# xc9572_dev_board_a.net
KiCad netlist of a schematic drawn in EAGLE
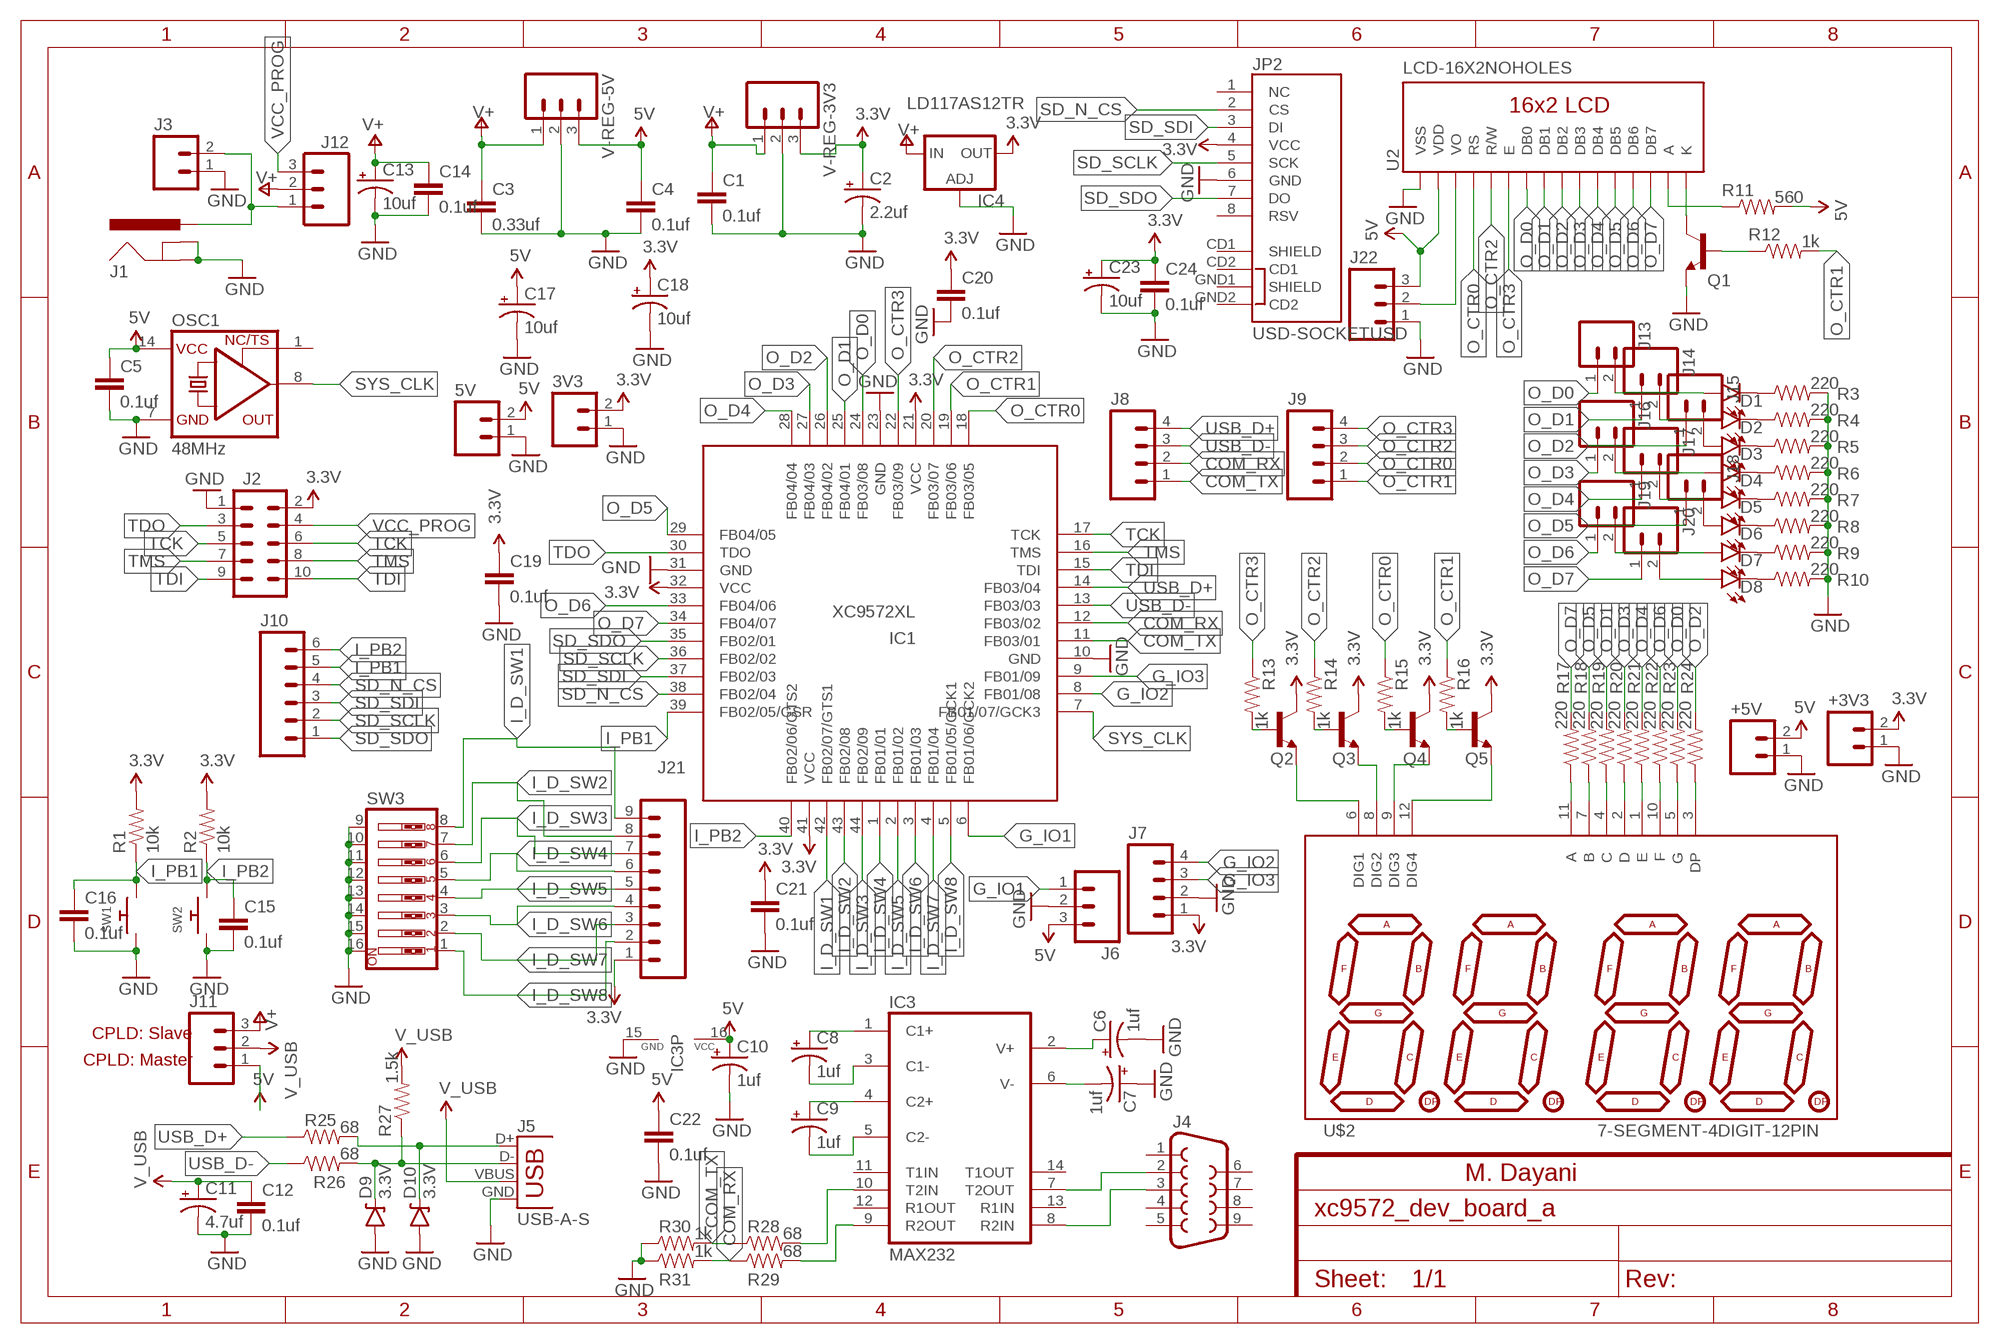
[diagram p0: schematic, sheet 1]

(export (version "E")
  (design (tool "Eeschema 10.0.6"))
  (components
    (comp (ref "+3V3")
      (value "M02JST-PTH-VERT")
      (footprint "eagle-import:JST-2-PTH-VERT")
      (libsource (lib "eagle-import") (part "M02JST-PTH-VERT"))
    )
    (comp (ref "+5V")
      (value "M02JST-PTH-VERT")
      (footprint "eagle-import:JST-2-PTH-VERT")
      (libsource (lib "eagle-import") (part "M02JST-PTH-VERT"))
    )
    (comp (ref "3V3")
      (value "M02PTH")
      (footprint "eagle-import:1X02")
      (libsource (lib "eagle-import") (part "M02PTH"))
    )
    (comp (ref "5V")
      (value "M02PTH")
      (footprint "eagle-import:1X02")
      (libsource (lib "eagle-import") (part "M02PTH"))
    )
    (comp (ref "C1")
      (value "0.1uf")
      (footprint "eagle-import:1206")
      (libsource (lib "eagle-import") (part "CAP1206"))
    )
    (comp (ref "C2")
      (value "2.2uf")
      (footprint "eagle-import:EIA3216")
      (libsource (lib "eagle-import") (part "CAP_POL1206"))
    )
    (comp (ref "C3")
      (value "0.33uf")
      (footprint "eagle-import:1206")
      (libsource (lib "eagle-import") (part "CAP1206"))
    )
    (comp (ref "C4")
      (value "0.1uf")
      (footprint "eagle-import:1206")
      (libsource (lib "eagle-import") (part "CAP1206"))
    )
    (comp (ref "C5")
      (value "0.1uf")
      (footprint "eagle-import:1206")
      (libsource (lib "eagle-import") (part "CAP1206"))
    )
    (comp (ref "C6")
      (value "1uf")
      (footprint "eagle-import:EIA3216")
      (libsource (lib "eagle-import") (part "CAP_POL1206"))
    )
    (comp (ref "C7")
      (value "1uf")
      (footprint "eagle-import:EIA3216")
      (libsource (lib "eagle-import") (part "CAP_POL1206"))
    )
    (comp (ref "C8")
      (value "1uf")
      (footprint "eagle-import:EIA3216")
      (libsource (lib "eagle-import") (part "CAP_POL1206"))
    )
    (comp (ref "C9")
      (value "1uf")
      (footprint "eagle-import:EIA3216")
      (libsource (lib "eagle-import") (part "CAP_POL1206"))
    )
    (comp (ref "C10")
      (value "1uf")
      (footprint "eagle-import:EIA3216")
      (libsource (lib "eagle-import") (part "CAP_POL1206"))
    )
    (comp (ref "C11")
      (value "4.7uf")
      (footprint "eagle-import:EIA3216")
      (libsource (lib "eagle-import") (part "CAP_POL1206"))
    )
    (comp (ref "C12")
      (value "0.1uf")
      (footprint "eagle-import:1206")
      (libsource (lib "eagle-import") (part "CAP1206"))
    )
    (comp (ref "C13")
      (value "10uf")
      (footprint "eagle-import:EIA3216")
      (libsource (lib "eagle-import") (part "CAP_POL1206"))
    )
    (comp (ref "C14")
      (value "0.1uf")
      (footprint "eagle-import:1206")
      (libsource (lib "eagle-import") (part "CAP1206"))
    )
    (comp (ref "C15")
      (value "0.1uf")
      (footprint "eagle-import:1206")
      (libsource (lib "eagle-import") (part "CAP1206"))
    )
    (comp (ref "C16")
      (value "0.1uf")
      (footprint "eagle-import:1206")
      (libsource (lib "eagle-import") (part "CAP1206"))
    )
    (comp (ref "C17")
      (value "10uf")
      (footprint "eagle-import:EIA3216")
      (libsource (lib "eagle-import") (part "CAP_POL1206"))
    )
    (comp (ref "C18")
      (value "10uf")
      (footprint "eagle-import:EIA3216")
      (libsource (lib "eagle-import") (part "CAP_POL1206"))
    )
    (comp (ref "C19")
      (value "0.1uf")
      (footprint "eagle-import:1206")
      (libsource (lib "eagle-import") (part "CAP1206"))
    )
    (comp (ref "C20")
      (value "0.1uf")
      (footprint "eagle-import:1206")
      (libsource (lib "eagle-import") (part "CAP1206"))
    )
    (comp (ref "C21")
      (value "0.1uf")
      (footprint "eagle-import:1206")
      (libsource (lib "eagle-import") (part "CAP1206"))
    )
    (comp (ref "C22")
      (value "0.1uf")
      (footprint "eagle-import:1206")
      (libsource (lib "eagle-import") (part "CAP1206"))
    )
    (comp (ref "C23")
      (value "10uf")
      (footprint "eagle-import:EIA3216")
      (libsource (lib "eagle-import") (part "CAP_POL1206"))
    )
    (comp (ref "C24")
      (value "0.1uf")
      (footprint "eagle-import:1206")
      (libsource (lib "eagle-import") (part "CAP1206"))
    )
    (comp (ref "D1")
      (value "LED1206")
      (footprint "eagle-import:LED-1206")
      (libsource (lib "eagle-import") (part "LED1206"))
    )
    (comp (ref "D2")
      (value "LED1206")
      (footprint "eagle-import:LED-1206")
      (libsource (lib "eagle-import") (part "LED1206"))
    )
    (comp (ref "D3")
      (value "LED1206")
      (footprint "eagle-import:LED-1206")
      (libsource (lib "eagle-import") (part "LED1206"))
    )
    (comp (ref "D4")
      (value "LED1206")
      (footprint "eagle-import:LED-1206")
      (libsource (lib "eagle-import") (part "LED1206"))
    )
    (comp (ref "D5")
      (value "LED1206")
      (footprint "eagle-import:LED-1206")
      (libsource (lib "eagle-import") (part "LED1206"))
    )
    (comp (ref "D6")
      (value "LED1206")
      (footprint "eagle-import:LED-1206")
      (libsource (lib "eagle-import") (part "LED1206"))
    )
    (comp (ref "D7")
      (value "LED1206")
      (footprint "eagle-import:LED-1206")
      (libsource (lib "eagle-import") (part "LED1206"))
    )
    (comp (ref "D8")
      (value "LED1206")
      (footprint "eagle-import:LED-1206")
      (libsource (lib "eagle-import") (part "LED1206"))
    )
    (comp (ref "D9")
      (value "3.3V")
      (footprint "eagle-import:SOD-323")
      (libsource (lib "eagle-import") (part "DIODE-ZENER3.3V"))
    )
    (comp (ref "D10")
      (value "3.3V")
      (footprint "eagle-import:SOD-323")
      (libsource (lib "eagle-import") (part "DIODE-ZENER3.3V"))
    )
    (comp (ref "IC1")
      (value "XC9572XL")
      (footprint "eagle-import:PLCC-S44")
      (libsource (lib "eagle-import") (part "XC9572XL"))
    )
    (comp (ref "IC3")
      (value "MAX232")
      (footprint "eagle-import:DIL16")
      (fields (field (name "MF") "MAXIM") (field (name "MPN") "MAX232ACPE+"))
      (libsource (lib "eagle-import") (part "MAX232"))
    )
    (comp (ref "IC4")
      (value "LD117AS12TR")
      (footprint "eagle-import:SOT223")
      (libsource (lib "eagle-import") (part "LD117A?S12TR"))
    )
    (comp (ref "J1")
      (value "POWER_JACKPTH_BREAD")
      (footprint "eagle-import:POWER_JACK_PTH_BREAD")
      (libsource (lib "eagle-import") (part "POWER_JACKPTH_BREAD"))
    )
    (comp (ref "J2")
      (value "M05X2SHD")
      (footprint "eagle-import:2X5-SHROUDED")
      (libsource (lib "eagle-import") (part "M05X2SHD"))
    )
    (comp (ref "J3")
      (value "M02JST-PTH-VERT")
      (footprint "eagle-import:JST-2-PTH-VERT")
      (libsource (lib "eagle-import") (part "M02JST-PTH-VERT"))
    )
    (comp (ref "J4")
      (value "DB9FEMALE")
      (footprint "eagle-import:DB9")
      (libsource (lib "eagle-import") (part "DB9FEMALE"))
    )
    (comp (ref "J5")
      (value "USB-A-S")
      (footprint "eagle-import:USB-A-S")
      (libsource (lib "eagle-import") (part "USB-A-S"))
    )
    (comp (ref "J6")
      (value "M03PTH")
      (footprint "eagle-import:1X03")
      (libsource (lib "eagle-import") (part "M03PTH"))
    )
    (comp (ref "J7")
      (value "M04PTH")
      (footprint "eagle-import:1X04")
      (libsource (lib "eagle-import") (part "M04PTH"))
    )
    (comp (ref "J8")
      (value "M04PTH")
      (footprint "eagle-import:1X04")
      (libsource (lib "eagle-import") (part "M04PTH"))
    )
    (comp (ref "J9")
      (value "M04PTH")
      (footprint "eagle-import:1X04")
      (libsource (lib "eagle-import") (part "M04PTH"))
    )
    (comp (ref "J10")
      (value "M06SILK_FEMALE_PTH")
      (footprint "eagle-import:1X06")
      (libsource (lib "eagle-import") (part "M06SILK_FEMALE_PTH"))
    )
    (comp (ref "J11")
      (value "M03PTH")
      (footprint "eagle-import:1X03")
      (libsource (lib "eagle-import") (part "M03PTH"))
    )
    (comp (ref "J12")
      (value "M03PTH")
      (footprint "eagle-import:1X03")
      (libsource (lib "eagle-import") (part "M03PTH"))
    )
    (comp (ref "J13")
      (value "M02PTH")
      (footprint "eagle-import:1X02")
      (libsource (lib "eagle-import") (part "M02PTH"))
    )
    (comp (ref "J14")
      (value "M02PTH")
      (footprint "eagle-import:1X02")
      (libsource (lib "eagle-import") (part "M02PTH"))
    )
    (comp (ref "J15")
      (value "M02PTH")
      (footprint "eagle-import:1X02")
      (libsource (lib "eagle-import") (part "M02PTH"))
    )
    (comp (ref "J16")
      (value "M02PTH")
      (footprint "eagle-import:1X02")
      (libsource (lib "eagle-import") (part "M02PTH"))
    )
    (comp (ref "J17")
      (value "M02PTH")
      (footprint "eagle-import:1X02")
      (libsource (lib "eagle-import") (part "M02PTH"))
    )
    (comp (ref "J18")
      (value "M02PTH")
      (footprint "eagle-import:1X02")
      (libsource (lib "eagle-import") (part "M02PTH"))
    )
    (comp (ref "J19")
      (value "M02PTH")
      (footprint "eagle-import:1X02")
      (libsource (lib "eagle-import") (part "M02PTH"))
    )
    (comp (ref "J20")
      (value "M02PTH")
      (footprint "eagle-import:1X02")
      (libsource (lib "eagle-import") (part "M02PTH"))
    )
    (comp (ref "J21")
      (value "M09")
      (footprint "eagle-import:1X09")
      (libsource (lib "eagle-import") (part "M09"))
    )
    (comp (ref "J22")
      (value "M03POLAR")
      (footprint "eagle-import:MOLEX-1X3")
      (libsource (lib "eagle-import") (part "M03POLAR"))
    )
    (comp (ref "JP2")
      (value "USD-SOCKETUSD")
      (footprint "eagle-import:USD-SOCKET-PP")
      (libsource (lib "eagle-import") (part "USD-SOCKETUSD"))
    )
    (comp (ref "OSC1")
      (value "48MHz")
      (footprint "eagle-import:DIL14S")
      (libsource (lib "eagle-import") (part "XO-14"))
    )
    (comp (ref "Q1")
      (value "TRANSISTOR_NPNSOT23-3")
      (footprint "eagle-import:SOT23-3")
      (libsource (lib "eagle-import") (part "TRANSISTOR_NPNSOT23-3"))
    )
    (comp (ref "Q2")
      (value "TRANSISTOR_NPNSOT23-3")
      (footprint "eagle-import:SOT23-3")
      (libsource (lib "eagle-import") (part "TRANSISTOR_NPNSOT23-3"))
    )
    (comp (ref "Q3")
      (value "TRANSISTOR_NPNSOT23-3")
      (footprint "eagle-import:SOT23-3")
      (libsource (lib "eagle-import") (part "TRANSISTOR_NPNSOT23-3"))
    )
    (comp (ref "Q4")
      (value "TRANSISTOR_NPNSOT23-3")
      (footprint "eagle-import:SOT23-3")
      (libsource (lib "eagle-import") (part "TRANSISTOR_NPNSOT23-3"))
    )
    (comp (ref "Q5")
      (value "TRANSISTOR_NPNSOT23-3")
      (footprint "eagle-import:SOT23-3")
      (libsource (lib "eagle-import") (part "TRANSISTOR_NPNSOT23-3"))
    )
    (comp (ref "R1")
      (value "10k")
      (footprint "eagle-import:1206")
      (libsource (lib "eagle-import") (part "RESISTOR1206"))
    )
    (comp (ref "R2")
      (value "10k")
      (footprint "eagle-import:1206")
      (libsource (lib "eagle-import") (part "RESISTOR1206"))
    )
    (comp (ref "R3")
      (value "220")
      (footprint "eagle-import:1206")
      (libsource (lib "eagle-import") (part "RESISTOR1206"))
    )
    (comp (ref "R4")
      (value "220")
      (footprint "eagle-import:1206")
      (libsource (lib "eagle-import") (part "RESISTOR1206"))
    )
    (comp (ref "R5")
      (value "220")
      (footprint "eagle-import:1206")
      (libsource (lib "eagle-import") (part "RESISTOR1206"))
    )
    (comp (ref "R6")
      (value "220")
      (footprint "eagle-import:1206")
      (libsource (lib "eagle-import") (part "RESISTOR1206"))
    )
    (comp (ref "R7")
      (value "220")
      (footprint "eagle-import:1206")
      (libsource (lib "eagle-import") (part "RESISTOR1206"))
    )
    (comp (ref "R8")
      (value "220")
      (footprint "eagle-import:1206")
      (libsource (lib "eagle-import") (part "RESISTOR1206"))
    )
    (comp (ref "R9")
      (value "220")
      (footprint "eagle-import:1206")
      (libsource (lib "eagle-import") (part "RESISTOR1206"))
    )
    (comp (ref "R10")
      (value "220")
      (footprint "eagle-import:1206")
      (libsource (lib "eagle-import") (part "RESISTOR1206"))
    )
    (comp (ref "R11")
      (value "560")
      (footprint "eagle-import:1206")
      (libsource (lib "eagle-import") (part "RESISTOR1206"))
    )
    (comp (ref "R12")
      (value "1k")
      (footprint "eagle-import:1206")
      (libsource (lib "eagle-import") (part "RESISTOR1206"))
    )
    (comp (ref "R13")
      (value "1k")
      (footprint "eagle-import:1206")
      (libsource (lib "eagle-import") (part "RESISTOR1206"))
    )
    (comp (ref "R14")
      (value "1k")
      (footprint "eagle-import:1206")
      (libsource (lib "eagle-import") (part "RESISTOR1206"))
    )
    (comp (ref "R15")
      (value "1k")
      (footprint "eagle-import:1206")
      (libsource (lib "eagle-import") (part "RESISTOR1206"))
    )
    (comp (ref "R16")
      (value "1k")
      (footprint "eagle-import:1206")
      (libsource (lib "eagle-import") (part "RESISTOR1206"))
    )
    (comp (ref "R17")
      (value "220")
      (footprint "eagle-import:1206")
      (libsource (lib "eagle-import") (part "RESISTOR1206"))
    )
    (comp (ref "R18")
      (value "220")
      (footprint "eagle-import:1206")
      (libsource (lib "eagle-import") (part "RESISTOR1206"))
    )
    (comp (ref "R19")
      (value "220")
      (footprint "eagle-import:1206")
      (libsource (lib "eagle-import") (part "RESISTOR1206"))
    )
    (comp (ref "R20")
      (value "220")
      (footprint "eagle-import:1206")
      (libsource (lib "eagle-import") (part "RESISTOR1206"))
    )
    (comp (ref "R21")
      (value "220")
      (footprint "eagle-import:1206")
      (libsource (lib "eagle-import") (part "RESISTOR1206"))
    )
    (comp (ref "R22")
      (value "220")
      (footprint "eagle-import:1206")
      (libsource (lib "eagle-import") (part "RESISTOR1206"))
    )
    (comp (ref "R23")
      (value "220")
      (footprint "eagle-import:1206")
      (libsource (lib "eagle-import") (part "RESISTOR1206"))
    )
    (comp (ref "R24")
      (value "220")
      (footprint "eagle-import:1206")
      (libsource (lib "eagle-import") (part "RESISTOR1206"))
    )
    (comp (ref "R25")
      (value "68")
      (footprint "eagle-import:1206")
      (libsource (lib "eagle-import") (part "RESISTOR1206"))
    )
    (comp (ref "R26")
      (value "68")
      (footprint "eagle-import:1206")
      (libsource (lib "eagle-import") (part "RESISTOR1206"))
    )
    (comp (ref "R27")
      (value "1.5k")
      (footprint "eagle-import:1206")
      (libsource (lib "eagle-import") (part "RESISTOR1206"))
    )
    (comp (ref "R28")
      (value "68")
      (footprint "eagle-import:1206")
      (libsource (lib "eagle-import") (part "RESISTOR1206"))
    )
    (comp (ref "R29")
      (value "68")
      (footprint "eagle-import:1206")
      (libsource (lib "eagle-import") (part "RESISTOR1206"))
    )
    (comp (ref "R30")
      (value "1k")
      (footprint "eagle-import:1206")
      (libsource (lib "eagle-import") (part "RESISTOR1206"))
    )
    (comp (ref "R31")
      (value "1k")
      (footprint "eagle-import:1206")
      (libsource (lib "eagle-import") (part "RESISTOR1206"))
    )
    (comp (ref "SW1")
      (value "SWITCH_PUSHBUTTONEVQ-PE")
      (footprint "eagle-import:TACT_PANA-EVQ")
      (libsource (lib "eagle-import") (part "SWITCH_PUSHBUTTONEVQ-PE"))
    )
    (comp (ref "SW2")
      (value "SWITCH_PUSHBUTTONEVQ-PE")
      (footprint "eagle-import:TACT_PANA-EVQ")
      (libsource (lib "eagle-import") (part "SWITCH_PUSHBUTTONEVQ-PE"))
    )
    (comp (ref "SW3")
      (value "SW_DIP-8")
      (footprint "eagle-import:DIPSWITCH-08")
      (libsource (lib "eagle-import") (part "SW_DIP-8"))
    )
    (comp (ref "U$2")
      (value "7-SEGMENT-4DIGIT-12PIN")
      (footprint "eagle-import:7-SEGMENT-4DIGIT-12PIN-LONGPADS")
      (libsource (lib "eagle-import") (part "7-SEGMENT-4DIGIT-12PIN"))
    )
    (comp (ref "U2")
      (value "LCD-16X2NOHOLES")
      (footprint "eagle-import:LCD-16X2_NOHOLES")
      (libsource (lib "eagle-import") (part "LCD-16X2NOHOLES"))
    )
    (comp (ref "V-REG-3V3")
      (value "M03PTH")
      (footprint "eagle-import:1X03")
      (libsource (lib "eagle-import") (part "M03PTH"))
    )
    (comp (ref "V-REG-5V")
      (value "M03PTH")
      (footprint "eagle-import:1X03")
      (libsource (lib "eagle-import") (part "M03PTH"))
    )
  )
  (nets
    (net (code "1") (name "3.3V") (class "Default")
      (node (ref "+3V3") (pin "2") (pinfunction "2_2") (pintype "passive"))
      (node (ref "3V3") (pin "2") (pinfunction "2_2") (pintype "passive"))
      (node (ref "C18") (pin "A") (pinfunction "+_A") (pintype "passive"))
      (node (ref "C19") (pin "1") (pinfunction "1_1") (pintype "passive"))
      (node (ref "C2") (pin "A") (pinfunction "+_A") (pintype "passive"))
      (node (ref "C20") (pin "1") (pinfunction "1_1") (pintype "passive"))
      (node (ref "C21") (pin "1") (pinfunction "1_1") (pintype "passive"))
      (node (ref "C23") (pin "A") (pinfunction "+_A") (pintype "passive"))
      (node (ref "C24") (pin "1") (pinfunction "1_1") (pintype "passive"))
      (node (ref "IC1") (pin "21") (pinfunction "VCC_21") (pintype "power_in"))
      (node (ref "IC1") (pin "32") (pinfunction "VCC_32") (pintype "power_in"))
      (node (ref "IC1") (pin "41") (pinfunction "VCC_41") (pintype "power_in"))
      (node (ref "IC4") (pin "4") (pinfunction "OUT_4") (pintype "passive"))
      (node (ref "J2") (pin "2") (pinfunction "2_2") (pintype "passive"))
      (node (ref "J21") (pin "1") (pinfunction "1_1") (pintype "passive"))
      (node (ref "J7") (pin "1") (pinfunction "1_1") (pintype "passive"))
      (node (ref "JP2") (pin "4") (pinfunction "VCC_4") (pintype "bidirectional"))
      (node (ref "Q2") (pin "3") (pinfunction "C_3") (pintype "passive"))
      (node (ref "Q3") (pin "3") (pinfunction "C_3") (pintype "passive"))
      (node (ref "Q4") (pin "3") (pinfunction "C_3") (pintype "passive"))
      (node (ref "Q5") (pin "3") (pinfunction "C_3") (pintype "passive"))
      (node (ref "R1") (pin "2") (pinfunction "2_2") (pintype "passive"))
      (node (ref "R2") (pin "2") (pinfunction "2_2") (pintype "passive"))
      (node (ref "V-REG-3V3") (pin "3") (pinfunction "3_3") (pintype "passive"))
    )
    (net (code "2") (name "5V") (class "Default")
      (node (ref "+5V") (pin "2") (pinfunction "2_2") (pintype "passive"))
      (node (ref "5V") (pin "2") (pinfunction "2_2") (pintype "passive"))
      (node (ref "C10") (pin "A") (pinfunction "+_A") (pintype "passive"))
      (node (ref "C17") (pin "A") (pinfunction "+_A") (pintype "passive"))
      (node (ref "C22") (pin "1") (pinfunction "1_1") (pintype "passive"))
      (node (ref "C4") (pin "1") (pinfunction "1_1") (pintype "passive"))
      (node (ref "C5") (pin "1") (pinfunction "1_1") (pintype "passive"))
      (node (ref "IC3") (pin "16") (pinfunction "VCC_16") (pintype "power_in"))
      (node (ref "J11") (pin "1") (pinfunction "1_1") (pintype "passive"))
      (node (ref "J22") (pin "3") (pinfunction "3_3") (pintype "passive"))
      (node (ref "J6") (pin "3") (pinfunction "3_3") (pintype "passive"))
      (node (ref "OSC1") (pin "14") (pinfunction "VCC_14") (pintype "power_in"))
      (node (ref "R11") (pin "2") (pinfunction "2_2") (pintype "passive"))
      (node (ref "U2") (pin "2") (pinfunction "VDD_2") (pintype "power_in"))
      (node (ref "V-REG-5V") (pin "3") (pinfunction "3_3") (pintype "passive"))
    )
    (net (code "3") (name "COM_RX") (class "Default")
      (node (ref "IC1") (pin "12") (pinfunction "FB03/02_12") (pintype "bidirectional"))
      (node (ref "J8") (pin "2") (pinfunction "2_2") (pintype "passive"))
      (node (ref "R29") (pin "1") (pinfunction "1_1") (pintype "passive"))
      (node (ref "R31") (pin "2") (pinfunction "2_2") (pintype "passive"))
    )
    (net (code "4") (name "COM_TX") (class "Default")
      (node (ref "IC1") (pin "11") (pinfunction "FB03/01_11") (pintype "bidirectional"))
      (node (ref "J8") (pin "1") (pinfunction "1_1") (pintype "passive"))
      (node (ref "R28") (pin "1") (pinfunction "1_1") (pintype "passive"))
      (node (ref "R30") (pin "2") (pinfunction "2_2") (pintype "passive"))
    )
    (net (code "5") (name "GND") (class "Default")
      (node (ref "+3V3") (pin "1") (pinfunction "1_1") (pintype "passive"))
      (node (ref "+5V") (pin "1") (pinfunction "1_1") (pintype "passive"))
      (node (ref "3V3") (pin "1") (pinfunction "1_1") (pintype "passive"))
      (node (ref "5V") (pin "1") (pinfunction "1_1") (pintype "passive"))
      (node (ref "C1") (pin "2") (pinfunction "2_2") (pintype "passive"))
      (node (ref "C10") (pin "C") (pinfunction "-_C") (pintype "passive"))
      (node (ref "C11") (pin "C") (pinfunction "-_C") (pintype "passive"))
      (node (ref "C12") (pin "2") (pinfunction "2_2") (pintype "passive"))
      (node (ref "C13") (pin "C") (pinfunction "-_C") (pintype "passive"))
      (node (ref "C14") (pin "2") (pinfunction "2_2") (pintype "passive"))
      (node (ref "C15") (pin "2") (pinfunction "2_2") (pintype "passive"))
      (node (ref "C16") (pin "2") (pinfunction "2_2") (pintype "passive"))
      (node (ref "C17") (pin "C") (pinfunction "-_C") (pintype "passive"))
      (node (ref "C18") (pin "C") (pinfunction "-_C") (pintype "passive"))
      (node (ref "C19") (pin "2") (pinfunction "2_2") (pintype "passive"))
      (node (ref "C2") (pin "C") (pinfunction "-_C") (pintype "passive"))
      (node (ref "C20") (pin "2") (pinfunction "2_2") (pintype "passive"))
      (node (ref "C21") (pin "2") (pinfunction "2_2") (pintype "passive"))
      (node (ref "C22") (pin "2") (pinfunction "2_2") (pintype "passive"))
      (node (ref "C23") (pin "C") (pinfunction "-_C") (pintype "passive"))
      (node (ref "C24") (pin "2") (pinfunction "2_2") (pintype "passive"))
      (node (ref "C3") (pin "2") (pinfunction "2_2") (pintype "passive"))
      (node (ref "C4") (pin "2") (pinfunction "2_2") (pintype "passive"))
      (node (ref "C5") (pin "2") (pinfunction "2_2") (pintype "passive"))
      (node (ref "C6") (pin "C") (pinfunction "-_C") (pintype "passive"))
      (node (ref "C7") (pin "A") (pinfunction "+_A") (pintype "passive"))
      (node (ref "D10") (pin "A") (pinfunction "A_A") (pintype "passive"))
      (node (ref "D9") (pin "A") (pinfunction "A_A") (pintype "passive"))
      (node (ref "IC1") (pin "10") (pinfunction "GND_10") (pintype "power_in"))
      (node (ref "IC1") (pin "23") (pinfunction "GND_23") (pintype "power_in"))
      (node (ref "IC1") (pin "31") (pinfunction "GND_31") (pintype "power_in"))
      (node (ref "IC3") (pin "15") (pinfunction "GND_15") (pintype "power_in"))
      (node (ref "IC4") (pin "1") (pinfunction "ADJ_1") (pintype "input"))
      (node (ref "J1") (pin "GND") (pinfunction "GND_GND") (pintype "bidirectional"))
      (node (ref "J1") (pin "GNDBREAK") (pinfunction "GNDBREAK_GNDBREAK") (pintype "bidirectional"))
      (node (ref "J2") (pin "1") (pinfunction "1_1") (pintype "passive"))
      (node (ref "J22") (pin "1") (pinfunction "1_1") (pintype "passive"))
      (node (ref "J3") (pin "1") (pinfunction "1_1") (pintype "passive"))
      (node (ref "J5") (pin "GND") (pinfunction "GND_GND") (pintype "bidirectional"))
      (node (ref "J6") (pin "2") (pinfunction "2_2") (pintype "passive"))
      (node (ref "J7") (pin "2") (pinfunction "2_2") (pintype "passive"))
      (node (ref "JP2") (pin "6") (pinfunction "GND_6") (pintype "bidirectional"))
      (node (ref "OSC1") (pin "7") (pinfunction "GND_7") (pintype "power_in"))
      (node (ref "Q1") (pin "2") (pinfunction "E_2") (pintype "passive"))
      (node (ref "R10") (pin "2") (pinfunction "2_2") (pintype "passive"))
      (node (ref "R3") (pin "2") (pinfunction "2_2") (pintype "passive"))
      (node (ref "R30") (pin "1") (pinfunction "1_1") (pintype "passive"))
      (node (ref "R31") (pin "1") (pinfunction "1_1") (pintype "passive"))
      (node (ref "R4") (pin "2") (pinfunction "2_2") (pintype "passive"))
      (node (ref "R5") (pin "2") (pinfunction "2_2") (pintype "passive"))
      (node (ref "R6") (pin "2") (pinfunction "2_2") (pintype "passive"))
      (node (ref "R7") (pin "2") (pinfunction "2_2") (pintype "passive"))
      (node (ref "R8") (pin "2") (pinfunction "2_2") (pintype "passive"))
      (node (ref "R9") (pin "2") (pinfunction "2_2") (pintype "passive"))
      (node (ref "SW1") (pin "P$1") (pinfunction "P$1_P$1") (pintype "passive"))
      (node (ref "SW2") (pin "P$1") (pinfunction "P$1_P$1") (pintype "passive"))
      (node (ref "SW3") (pin "10") (pinfunction "10_10") (pintype "passive"))
      (node (ref "SW3") (pin "11") (pinfunction "11_11") (pintype "passive"))
      (node (ref "SW3") (pin "12") (pinfunction "12_12") (pintype "passive"))
      (node (ref "SW3") (pin "13") (pinfunction "13_13") (pintype "passive"))
      (node (ref "SW3") (pin "14") (pinfunction "14_14") (pintype "passive"))
      (node (ref "SW3") (pin "15") (pinfunction "15_15") (pintype "passive"))
      (node (ref "SW3") (pin "16") (pinfunction "16_16") (pintype "passive"))
      (node (ref "SW3") (pin "9") (pinfunction "9_9") (pintype "passive"))
      (node (ref "U2") (pin "1") (pinfunction "VSS_1") (pintype "power_in"))
      (node (ref "V-REG-3V3") (pin "2") (pinfunction "2_2") (pintype "passive"))
      (node (ref "V-REG-5V") (pin "2") (pinfunction "2_2") (pintype "passive"))
    )
    (net (code "6") (name "G_IO1") (class "Default")
      (node (ref "IC1") (pin "6") (pinfunction "FB01/06/GCK2_6") (pintype "bidirectional"))
      (node (ref "J6") (pin "1") (pinfunction "1_1") (pintype "passive"))
    )
    (net (code "7") (name "G_IO2") (class "Default")
      (node (ref "IC1") (pin "8") (pinfunction "FB01/08_8") (pintype "bidirectional"))
      (node (ref "J7") (pin "4") (pinfunction "4_4") (pintype "passive"))
    )
    (net (code "8") (name "G_IO3") (class "Default")
      (node (ref "IC1") (pin "9") (pinfunction "FB01/09_9") (pintype "bidirectional"))
      (node (ref "J7") (pin "3") (pinfunction "3_3") (pintype "passive"))
    )
    (net (code "9") (name "I_D_SW1") (class "Default")
      (node (ref "IC1") (pin "42") (pinfunction "FB02/07/GTS1_42") (pintype "bidirectional"))
      (node (ref "J21") (pin "9") (pinfunction "9_9") (pintype "passive"))
      (node (ref "SW3") (pin "8") (pinfunction "8_8") (pintype "passive"))
    )
    (net (code "10") (name "I_D_SW2") (class "Default")
      (node (ref "IC1") (pin "43") (pinfunction "FB02/08_43") (pintype "bidirectional"))
      (node (ref "J21") (pin "8") (pinfunction "8_8") (pintype "passive"))
      (node (ref "SW3") (pin "7") (pinfunction "7_7") (pintype "passive"))
    )
    (net (code "11") (name "I_D_SW3") (class "Default")
      (node (ref "IC1") (pin "44") (pinfunction "FB02/09_44") (pintype "bidirectional"))
      (node (ref "J21") (pin "7") (pinfunction "7_7") (pintype "passive"))
      (node (ref "SW3") (pin "6") (pinfunction "6_6") (pintype "passive"))
    )
    (net (code "12") (name "I_D_SW4") (class "Default")
      (node (ref "IC1") (pin "1") (pinfunction "FB01/01_1") (pintype "bidirectional"))
      (node (ref "J21") (pin "6") (pinfunction "6_6") (pintype "passive"))
      (node (ref "SW3") (pin "5") (pinfunction "5_5") (pintype "passive"))
    )
    (net (code "13") (name "I_D_SW5") (class "Default")
      (node (ref "IC1") (pin "2") (pinfunction "FB01/02_2") (pintype "bidirectional"))
      (node (ref "J21") (pin "5") (pinfunction "5_5") (pintype "passive"))
      (node (ref "SW3") (pin "4") (pinfunction "4_4") (pintype "passive"))
    )
    (net (code "14") (name "I_D_SW6") (class "Default")
      (node (ref "IC1") (pin "3") (pinfunction "FB01/03_3") (pintype "bidirectional"))
      (node (ref "J21") (pin "4") (pinfunction "4_4") (pintype "passive"))
      (node (ref "SW3") (pin "3") (pinfunction "3_3") (pintype "passive"))
    )
    (net (code "15") (name "I_D_SW7") (class "Default")
      (node (ref "IC1") (pin "4") (pinfunction "FB01/04_4") (pintype "bidirectional"))
      (node (ref "J21") (pin "3") (pinfunction "3_3") (pintype "passive"))
      (node (ref "SW3") (pin "2") (pinfunction "2_2") (pintype "passive"))
    )
    (net (code "16") (name "I_D_SW8") (class "Default")
      (node (ref "IC1") (pin "5") (pinfunction "FB01/05/GCK1_5") (pintype "bidirectional"))
      (node (ref "J21") (pin "2") (pinfunction "2_2") (pintype "passive"))
      (node (ref "SW3") (pin "1") (pinfunction "1_1") (pintype "passive"))
    )
    (net (code "17") (name "I_PB1") (class "Default")
      (node (ref "C16") (pin "1") (pinfunction "1_1") (pintype "passive"))
      (node (ref "IC1") (pin "39") (pinfunction "FB02/05/GSR_39") (pintype "bidirectional"))
      (node (ref "J10") (pin "5") (pinfunction "5_5") (pintype "passive"))
      (node (ref "R1") (pin "1") (pinfunction "1_1") (pintype "passive"))
      (node (ref "SW1") (pin "P$2") (pinfunction "P$2_P$2") (pintype "passive"))
    )
    (net (code "18") (name "I_PB2") (class "Default")
      (node (ref "C15") (pin "1") (pinfunction "1_1") (pintype "passive"))
      (node (ref "IC1") (pin "40") (pinfunction "FB02/06/GTS2_40") (pintype "bidirectional"))
      (node (ref "J10") (pin "6") (pinfunction "6_6") (pintype "passive"))
      (node (ref "R2") (pin "1") (pinfunction "1_1") (pintype "passive"))
      (node (ref "SW2") (pin "P$2") (pinfunction "P$2_P$2") (pintype "passive"))
    )
    (net (code "19") (name "Net-(C6-+)") (class "Default")
      (node (ref "C6") (pin "A") (pinfunction "+_A") (pintype "passive"))
      (node (ref "IC3") (pin "2") (pinfunction "V+_2") (pintype "bidirectional"))
    )
    (net (code "20") (name "Net-(C7--)") (class "Default")
      (node (ref "C7") (pin "C") (pinfunction "-_C") (pintype "passive"))
      (node (ref "IC3") (pin "6") (pinfunction "V-_6") (pintype "bidirectional"))
    )
    (net (code "21") (name "Net-(C8-+)") (class "Default")
      (node (ref "C8") (pin "A") (pinfunction "+_A") (pintype "passive"))
      (node (ref "IC3") (pin "1") (pinfunction "C1+_1") (pintype "bidirectional"))
    )
    (net (code "22") (name "Net-(C8--)") (class "Default")
      (node (ref "C8") (pin "C") (pinfunction "-_C") (pintype "passive"))
      (node (ref "IC3") (pin "3") (pinfunction "C1-_3") (pintype "bidirectional"))
    )
    (net (code "23") (name "Net-(C9-+)") (class "Default")
      (node (ref "C9") (pin "A") (pinfunction "+_A") (pintype "passive"))
      (node (ref "IC3") (pin "4") (pinfunction "C2+_4") (pintype "bidirectional"))
    )
    (net (code "24") (name "Net-(C9--)") (class "Default")
      (node (ref "C9") (pin "C") (pinfunction "-_C") (pintype "passive"))
      (node (ref "IC3") (pin "5") (pinfunction "C2-_5") (pintype "bidirectional"))
    )
    (net (code "25") (name "Net-(D1-PadA)") (class "Default")
      (node (ref "D1") (pin "A") (pinfunction "A_A") (pintype "passive"))
      (node (ref "J13") (pin "2") (pinfunction "2_2") (pintype "passive"))
    )
    (net (code "26") (name "Net-(D1-PadC)") (class "Default")
      (node (ref "D1") (pin "C") (pinfunction "C_C") (pintype "passive"))
      (node (ref "R3") (pin "1") (pinfunction "1_1") (pintype "passive"))
    )
    (net (code "27") (name "Net-(D2-PadA)") (class "Default")
      (node (ref "D2") (pin "A") (pinfunction "A_A") (pintype "passive"))
      (node (ref "J14") (pin "2") (pinfunction "2_2") (pintype "passive"))
    )
    (net (code "28") (name "Net-(D2-PadC)") (class "Default")
      (node (ref "D2") (pin "C") (pinfunction "C_C") (pintype "passive"))
      (node (ref "R4") (pin "1") (pinfunction "1_1") (pintype "passive"))
    )
    (net (code "29") (name "Net-(D3-PadA)") (class "Default")
      (node (ref "D3") (pin "A") (pinfunction "A_A") (pintype "passive"))
      (node (ref "J15") (pin "2") (pinfunction "2_2") (pintype "passive"))
    )
    (net (code "30") (name "Net-(D3-PadC)") (class "Default")
      (node (ref "D3") (pin "C") (pinfunction "C_C") (pintype "passive"))
      (node (ref "R5") (pin "1") (pinfunction "1_1") (pintype "passive"))
    )
    (net (code "31") (name "Net-(D4-PadA)") (class "Default")
      (node (ref "D4") (pin "A") (pinfunction "A_A") (pintype "passive"))
      (node (ref "J16") (pin "2") (pinfunction "2_2") (pintype "passive"))
    )
    (net (code "32") (name "Net-(D4-PadC)") (class "Default")
      (node (ref "D4") (pin "C") (pinfunction "C_C") (pintype "passive"))
      (node (ref "R6") (pin "1") (pinfunction "1_1") (pintype "passive"))
    )
    (net (code "33") (name "Net-(D5-PadA)") (class "Default")
      (node (ref "D5") (pin "A") (pinfunction "A_A") (pintype "passive"))
      (node (ref "J17") (pin "2") (pinfunction "2_2") (pintype "passive"))
    )
    (net (code "34") (name "Net-(D5-PadC)") (class "Default")
      (node (ref "D5") (pin "C") (pinfunction "C_C") (pintype "passive"))
      (node (ref "R7") (pin "1") (pinfunction "1_1") (pintype "passive"))
    )
    (net (code "35") (name "Net-(D6-PadA)") (class "Default")
      (node (ref "D6") (pin "A") (pinfunction "A_A") (pintype "passive"))
      (node (ref "J18") (pin "2") (pinfunction "2_2") (pintype "passive"))
    )
    (net (code "36") (name "Net-(D6-PadC)") (class "Default")
      (node (ref "D6") (pin "C") (pinfunction "C_C") (pintype "passive"))
      (node (ref "R8") (pin "1") (pinfunction "1_1") (pintype "passive"))
    )
    (net (code "37") (name "Net-(D7-PadA)") (class "Default")
      (node (ref "D7") (pin "A") (pinfunction "A_A") (pintype "passive"))
      (node (ref "J19") (pin "2") (pinfunction "2_2") (pintype "passive"))
    )
    (net (code "38") (name "Net-(D7-PadC)") (class "Default")
      (node (ref "D7") (pin "C") (pinfunction "C_C") (pintype "passive"))
      (node (ref "R9") (pin "1") (pinfunction "1_1") (pintype "passive"))
    )
    (net (code "39") (name "Net-(D8-PadA)") (class "Default")
      (node (ref "D8") (pin "A") (pinfunction "A_A") (pintype "passive"))
      (node (ref "J20") (pin "2") (pinfunction "2_2") (pintype "passive"))
    )
    (net (code "40") (name "Net-(D8-PadC)") (class "Default")
      (node (ref "D8") (pin "C") (pinfunction "C_C") (pintype "passive"))
      (node (ref "R10") (pin "1") (pinfunction "1_1") (pintype "passive"))
    )
    (net (code "41") (name "Net-(D9-PadC)") (class "Default")
      (node (ref "D9") (pin "C") (pinfunction "C_C") (pintype "passive"))
      (node (ref "J5") (pin "D-") (pinfunction "D-_D-") (pintype "bidirectional"))
      (node (ref "R26") (pin "2") (pinfunction "2_2") (pintype "passive"))
      (node (ref "R27") (pin "1") (pinfunction "1_1") (pintype "passive"))
    )
    (net (code "42") (name "Net-(D10-PadC)") (class "Default")
      (node (ref "D10") (pin "C") (pinfunction "C_C") (pintype "passive"))
      (node (ref "J5") (pin "D+") (pinfunction "D+_D+") (pintype "bidirectional"))
      (node (ref "R25") (pin "2") (pinfunction "2_2") (pintype "passive"))
    )
    (net (code "43") (name "Net-(IC3A-R2IN)") (class "Default")
      (node (ref "IC3") (pin "8") (pinfunction "R2IN_8") (pintype "input"))
      (node (ref "J4") (pin "3") (pinfunction "3_3") (pintype "passive"))
    )
    (net (code "44") (name "Net-(IC3A-R2OUT)") (class "Default")
      (node (ref "IC3") (pin "9") (pinfunction "R2OUT_9") (pintype "output"))
      (node (ref "R29") (pin "2") (pinfunction "2_2") (pintype "passive"))
    )
    (net (code "45") (name "Net-(IC3A-T2IN)") (class "Default")
      (node (ref "IC3") (pin "10") (pinfunction "T2IN_10") (pintype "input"))
      (node (ref "R28") (pin "2") (pinfunction "2_2") (pintype "passive"))
    )
    (net (code "46") (name "Net-(IC3A-T2OUT)") (class "Default")
      (node (ref "IC3") (pin "7") (pinfunction "T2OUT_7") (pintype "output"))
      (node (ref "J4") (pin "2") (pinfunction "2_2") (pintype "passive"))
    )
    (net (code "47") (name "Net-(J1-PadPWR)") (class "Default")
      (node (ref "J1") (pin "PWR") (pinfunction "PWR_PWR") (pintype "bidirectional"))
      (node (ref "J12") (pin "1") (pinfunction "1_1") (pintype "passive"))
      (node (ref "J3") (pin "2") (pinfunction "2_2") (pintype "passive"))
    )
    (net (code "48") (name "Net-(Q1-B)") (class "Default")
      (node (ref "Q1") (pin "1") (pinfunction "B_1") (pintype "passive"))
      (node (ref "R12") (pin "1") (pinfunction "1_1") (pintype "passive"))
    )
    (net (code "49") (name "Net-(Q1-C)") (class "Default")
      (node (ref "Q1") (pin "3") (pinfunction "C_3") (pintype "passive"))
      (node (ref "U2") (pin "16") (pinfunction "K_16") (pintype "power_in"))
    )
    (net (code "50") (name "Net-(Q2-B)") (class "Default")
      (node (ref "Q2") (pin "1") (pinfunction "B_1") (pintype "passive"))
      (node (ref "R13") (pin "2") (pinfunction "2_2") (pintype "passive"))
    )
    (net (code "51") (name "Net-(Q2-E)") (class "Default")
      (node (ref "Q2") (pin "2") (pinfunction "E_2") (pintype "passive"))
      (node (ref "U$2") (pin "6") (pinfunction "DIG1_6") (pintype "bidirectional"))
    )
    (net (code "52") (name "Net-(Q3-B)") (class "Default")
      (node (ref "Q3") (pin "1") (pinfunction "B_1") (pintype "passive"))
      (node (ref "R14") (pin "2") (pinfunction "2_2") (pintype "passive"))
    )
    (net (code "53") (name "Net-(Q3-E)") (class "Default")
      (node (ref "Q3") (pin "2") (pinfunction "E_2") (pintype "passive"))
      (node (ref "U$2") (pin "8") (pinfunction "DIG2_8") (pintype "bidirectional"))
    )
    (net (code "54") (name "Net-(Q4-B)") (class "Default")
      (node (ref "Q4") (pin "1") (pinfunction "B_1") (pintype "passive"))
      (node (ref "R15") (pin "2") (pinfunction "2_2") (pintype "passive"))
    )
    (net (code "55") (name "Net-(Q4-E)") (class "Default")
      (node (ref "Q4") (pin "2") (pinfunction "E_2") (pintype "passive"))
      (node (ref "U$2") (pin "9") (pinfunction "DIG3_9") (pintype "bidirectional"))
    )
    (net (code "56") (name "Net-(Q5-B)") (class "Default")
      (node (ref "Q5") (pin "1") (pinfunction "B_1") (pintype "passive"))
      (node (ref "R16") (pin "2") (pinfunction "2_2") (pintype "passive"))
    )
    (net (code "57") (name "Net-(Q5-E)") (class "Default")
      (node (ref "Q5") (pin "2") (pinfunction "E_2") (pintype "passive"))
      (node (ref "U$2") (pin "12") (pinfunction "DIG4_12") (pintype "bidirectional"))
    )
    (net (code "58") (name "Net-(U$2-A)") (class "Default")
      (node (ref "R17") (pin "1") (pinfunction "1_1") (pintype "passive"))
      (node (ref "U$2") (pin "11") (pinfunction "A_11") (pintype "bidirectional"))
    )
    (net (code "59") (name "Net-(U$2-B)") (class "Default")
      (node (ref "R18") (pin "1") (pinfunction "1_1") (pintype "passive"))
      (node (ref "U$2") (pin "7") (pinfunction "B_7") (pintype "bidirectional"))
    )
    (net (code "60") (name "Net-(U$2-C)") (class "Default")
      (node (ref "R19") (pin "1") (pinfunction "1_1") (pintype "passive"))
      (node (ref "U$2") (pin "4") (pinfunction "C_4") (pintype "bidirectional"))
    )
    (net (code "61") (name "Net-(U$2-D)") (class "Default")
      (node (ref "R20") (pin "1") (pinfunction "1_1") (pintype "passive"))
      (node (ref "U$2") (pin "2") (pinfunction "D_2") (pintype "bidirectional"))
    )
    (net (code "62") (name "Net-(U$2-DP)") (class "Default")
      (node (ref "R24") (pin "1") (pinfunction "1_1") (pintype "passive"))
      (node (ref "U$2") (pin "3") (pinfunction "DP_3") (pintype "bidirectional"))
    )
    (net (code "63") (name "Net-(U$2-E)") (class "Default")
      (node (ref "R21") (pin "1") (pinfunction "1_1") (pintype "passive"))
      (node (ref "U$2") (pin "1") (pinfunction "E_1") (pintype "bidirectional"))
    )
    (net (code "64") (name "Net-(U$2-F)") (class "Default")
      (node (ref "R22") (pin "1") (pinfunction "1_1") (pintype "passive"))
      (node (ref "U$2") (pin "10") (pinfunction "F_10") (pintype "bidirectional"))
    )
    (net (code "65") (name "Net-(U$2-G)") (class "Default")
      (node (ref "R23") (pin "1") (pinfunction "1_1") (pintype "passive"))
      (node (ref "U$2") (pin "5") (pinfunction "G_5") (pintype "bidirectional"))
    )
    (net (code "66") (name "Net-(U2-A)") (class "Default")
      (node (ref "R11") (pin "1") (pinfunction "1_1") (pintype "passive"))
      (node (ref "U2") (pin "15") (pinfunction "A_15") (pintype "power_in"))
    )
    (net (code "67") (name "Net-(U2-VO)") (class "Default")
      (node (ref "J22") (pin "2") (pinfunction "2_2") (pintype "passive"))
      (node (ref "U2") (pin "3") (pinfunction "VO_3") (pintype "bidirectional"))
    )
    (net (code "68") (name "O_CTR0") (class "Default")
      (node (ref "IC1") (pin "18") (pinfunction "FB03/05_18") (pintype "bidirectional"))
      (node (ref "J9") (pin "2") (pinfunction "2_2") (pintype "passive"))
      (node (ref "R15") (pin "1") (pinfunction "1_1") (pintype "passive"))
      (node (ref "U2") (pin "4") (pinfunction "RS_4") (pintype "input"))
    )
    (net (code "69") (name "O_CTR1") (class "Default")
      (node (ref "IC1") (pin "19") (pinfunction "FB03/06_19") (pintype "bidirectional"))
      (node (ref "J9") (pin "1") (pinfunction "1_1") (pintype "passive"))
      (node (ref "R12") (pin "2") (pinfunction "2_2") (pintype "passive"))
      (node (ref "R16") (pin "1") (pinfunction "1_1") (pintype "passive"))
    )
    (net (code "70") (name "O_CTR2") (class "Default")
      (node (ref "IC1") (pin "20") (pinfunction "FB03/07_20") (pintype "bidirectional"))
      (node (ref "J9") (pin "3") (pinfunction "3_3") (pintype "passive"))
      (node (ref "R14") (pin "1") (pinfunction "1_1") (pintype "passive"))
      (node (ref "U2") (pin "5") (pinfunction "R/W_5") (pintype "input"))
    )
    (net (code "71") (name "O_CTR3") (class "Default")
      (node (ref "IC1") (pin "22") (pinfunction "FB03/09_22") (pintype "bidirectional"))
      (node (ref "J9") (pin "4") (pinfunction "4_4") (pintype "passive"))
      (node (ref "R13") (pin "1") (pinfunction "1_1") (pintype "passive"))
      (node (ref "U2") (pin "6") (pinfunction "E_6") (pintype "input"))
    )
    (net (code "72") (name "O_D0") (class "Default")
      (node (ref "IC1") (pin "24") (pinfunction "FB03/08_24") (pintype "bidirectional"))
      (node (ref "J13") (pin "1") (pinfunction "1_1") (pintype "passive"))
      (node (ref "R23") (pin "2") (pinfunction "2_2") (pintype "passive"))
      (node (ref "U2") (pin "7") (pinfunction "DB0_7") (pintype "bidirectional"))
    )
    (net (code "73") (name "O_D1") (class "Default")
      (node (ref "IC1") (pin "25") (pinfunction "FB04/01_25") (pintype "bidirectional"))
      (node (ref "J14") (pin "1") (pinfunction "1_1") (pintype "passive"))
      (node (ref "R19") (pin "2") (pinfunction "2_2") (pintype "passive"))
      (node (ref "U2") (pin "8") (pinfunction "DB1_8") (pintype "bidirectional"))
    )
    (net (code "74") (name "O_D2") (class "Default")
      (node (ref "IC1") (pin "26") (pinfunction "FB04/02_26") (pintype "bidirectional"))
      (node (ref "J15") (pin "1") (pinfunction "1_1") (pintype "passive"))
      (node (ref "R24") (pin "2") (pinfunction "2_2") (pintype "passive"))
      (node (ref "U2") (pin "9") (pinfunction "DB2_9") (pintype "bidirectional"))
    )
    (net (code "75") (name "O_D3") (class "Default")
      (node (ref "IC1") (pin "27") (pinfunction "FB04/03_27") (pintype "bidirectional"))
      (node (ref "J16") (pin "1") (pinfunction "1_1") (pintype "passive"))
      (node (ref "R20") (pin "2") (pinfunction "2_2") (pintype "passive"))
      (node (ref "U2") (pin "10") (pinfunction "DB3_10") (pintype "bidirectional"))
    )
    (net (code "76") (name "O_D4") (class "Default")
      (node (ref "IC1") (pin "28") (pinfunction "FB04/04_28") (pintype "bidirectional"))
      (node (ref "J17") (pin "1") (pinfunction "1_1") (pintype "passive"))
      (node (ref "R21") (pin "2") (pinfunction "2_2") (pintype "passive"))
      (node (ref "U2") (pin "11") (pinfunction "DB4_11") (pintype "bidirectional"))
    )
    (net (code "77") (name "O_D5") (class "Default")
      (node (ref "IC1") (pin "29") (pinfunction "FB04/05_29") (pintype "bidirectional"))
      (node (ref "J18") (pin "1") (pinfunction "1_1") (pintype "passive"))
      (node (ref "R18") (pin "2") (pinfunction "2_2") (pintype "passive"))
      (node (ref "U2") (pin "12") (pinfunction "DB5_12") (pintype "bidirectional"))
    )
    (net (code "78") (name "O_D6") (class "Default")
      (node (ref "IC1") (pin "33") (pinfunction "FB04/06_33") (pintype "bidirectional"))
      (node (ref "J19") (pin "1") (pinfunction "1_1") (pintype "passive"))
      (node (ref "R22") (pin "2") (pinfunction "2_2") (pintype "passive"))
      (node (ref "U2") (pin "13") (pinfunction "DB6_13") (pintype "bidirectional"))
    )
    (net (code "79") (name "O_D7") (class "Default")
      (node (ref "IC1") (pin "34") (pinfunction "FB04/07_34") (pintype "bidirectional"))
      (node (ref "J20") (pin "1") (pinfunction "1_1") (pintype "passive"))
      (node (ref "R17") (pin "2") (pinfunction "2_2") (pintype "passive"))
      (node (ref "U2") (pin "14") (pinfunction "DB7_14") (pintype "bidirectional"))
    )
    (net (code "80") (name "SD_N_CS") (class "Default")
      (node (ref "IC1") (pin "38") (pinfunction "FB02/04_38") (pintype "bidirectional"))
      (node (ref "J10") (pin "4") (pinfunction "4_4") (pintype "passive"))
      (node (ref "JP2") (pin "2") (pinfunction "CS_2") (pintype "bidirectional"))
    )
    (net (code "81") (name "SD_SCLK") (class "Default")
      (node (ref "IC1") (pin "36") (pinfunction "FB02/02_36") (pintype "bidirectional"))
      (node (ref "J10") (pin "2") (pinfunction "2_2") (pintype "passive"))
      (node (ref "JP2") (pin "5") (pinfunction "SCK_5") (pintype "bidirectional"))
    )
    (net (code "82") (name "SD_SDI") (class "Default")
      (node (ref "IC1") (pin "37") (pinfunction "FB02/03_37") (pintype "bidirectional"))
      (node (ref "J10") (pin "3") (pinfunction "3_3") (pintype "passive"))
      (node (ref "JP2") (pin "3") (pinfunction "DI_3") (pintype "bidirectional"))
    )
    (net (code "83") (name "SD_SDO") (class "Default")
      (node (ref "IC1") (pin "35") (pinfunction "FB02/01_35") (pintype "bidirectional"))
      (node (ref "J10") (pin "1") (pinfunction "1_1") (pintype "passive"))
      (node (ref "JP2") (pin "7") (pinfunction "DO_7") (pintype "bidirectional"))
    )
    (net (code "84") (name "SYS_CLK") (class "Default")
      (node (ref "IC1") (pin "7") (pinfunction "FB01/07/GCK3_7") (pintype "bidirectional"))
      (node (ref "OSC1") (pin "8") (pinfunction "OUT_8") (pintype "output"))
    )
    (net (code "85") (name "TCK") (class "Default")
      (node (ref "IC1") (pin "17") (pinfunction "TCK_17") (pintype "input"))
      (node (ref "J2") (pin "5") (pinfunction "5_5") (pintype "passive"))
      (node (ref "J2") (pin "6") (pinfunction "6_6") (pintype "passive"))
    )
    (net (code "86") (name "TDI") (class "Default")
      (node (ref "IC1") (pin "15") (pinfunction "TDI_15") (pintype "input"))
      (node (ref "J2") (pin "10") (pinfunction "10_10") (pintype "passive"))
      (node (ref "J2") (pin "9") (pinfunction "9_9") (pintype "passive"))
    )
    (net (code "87") (name "TDO") (class "Default")
      (node (ref "IC1") (pin "30") (pinfunction "TDO_30") (pintype "output"))
      (node (ref "J2") (pin "3") (pinfunction "3_3") (pintype "passive"))
    )
    (net (code "88") (name "TMS") (class "Default")
      (node (ref "IC1") (pin "16") (pinfunction "TMS_16") (pintype "input"))
      (node (ref "J2") (pin "7") (pinfunction "7_7") (pintype "passive"))
      (node (ref "J2") (pin "8") (pinfunction "8_8") (pintype "passive"))
    )
    (net (code "89") (name "USB_D+") (class "Default")
      (node (ref "IC1") (pin "14") (pinfunction "FB03/04_14") (pintype "bidirectional"))
      (node (ref "J8") (pin "4") (pinfunction "4_4") (pintype "passive"))
      (node (ref "R25") (pin "1") (pinfunction "1_1") (pintype "passive"))
    )
    (net (code "90") (name "USB_D-") (class "Default")
      (node (ref "IC1") (pin "13") (pinfunction "FB03/03_13") (pintype "bidirectional"))
      (node (ref "J8") (pin "3") (pinfunction "3_3") (pintype "passive"))
      (node (ref "R26") (pin "1") (pinfunction "1_1") (pintype "passive"))
    )
    (net (code "91") (name "V+") (class "Default")
      (node (ref "C1") (pin "1") (pinfunction "1_1") (pintype "passive"))
      (node (ref "C13") (pin "A") (pinfunction "+_A") (pintype "passive"))
      (node (ref "C14") (pin "1") (pinfunction "1_1") (pintype "passive"))
      (node (ref "C3") (pin "1") (pinfunction "1_1") (pintype "passive"))
      (node (ref "IC4") (pin "3") (pinfunction "IN_3") (pintype "input"))
      (node (ref "J11") (pin "3") (pinfunction "3_3") (pintype "passive"))
      (node (ref "J12") (pin "2") (pinfunction "2_2") (pintype "passive"))
      (node (ref "V-REG-3V3") (pin "1") (pinfunction "1_1") (pintype "passive"))
      (node (ref "V-REG-5V") (pin "1") (pinfunction "1_1") (pintype "passive"))
    )
    (net (code "92") (name "VCC_PROG") (class "Default")
      (node (ref "J12") (pin "3") (pinfunction "3_3") (pintype "passive"))
      (node (ref "J2") (pin "4") (pinfunction "4_4") (pintype "passive"))
    )
    (net (code "93") (name "V_USB") (class "Default")
      (node (ref "C11") (pin "A") (pinfunction "+_A") (pintype "passive"))
      (node (ref "C12") (pin "1") (pinfunction "1_1") (pintype "passive"))
      (node (ref "J11") (pin "2") (pinfunction "2_2") (pintype "passive"))
      (node (ref "J5") (pin "VBUS") (pinfunction "VBUS_VBUS") (pintype "bidirectional"))
      (node (ref "R27") (pin "2") (pinfunction "2_2") (pintype "passive"))
    )
    (net (code "94") (name "unconnected-(IC3A-R1IN-Pad13)") (class "Default")
      (node (ref "IC3") (pin "13") (pinfunction "R1IN_13") (pintype "input"))
    )
    (net (code "95") (name "unconnected-(IC3A-R1OUT-Pad12)") (class "Default")
      (node (ref "IC3") (pin "12") (pinfunction "R1OUT_12") (pintype "output"))
    )
    (net (code "96") (name "unconnected-(IC3A-T1IN-Pad11)") (class "Default")
      (node (ref "IC3") (pin "11") (pinfunction "T1IN_11") (pintype "input"))
    )
    (net (code "97") (name "unconnected-(IC3A-T1OUT-Pad14)") (class "Default")
      (node (ref "IC3") (pin "14") (pinfunction "T1OUT_14") (pintype "output"))
    )
    (net (code "98") (name "unconnected-(J4-Pad1)") (class "Default")
      (node (ref "J4") (pin "1") (pinfunction "1_1") (pintype "passive"))
    )
    (net (code "99") (name "unconnected-(J4-Pad4)") (class "Default")
      (node (ref "J4") (pin "4") (pinfunction "4_4") (pintype "passive"))
    )
    (net (code "100") (name "unconnected-(J4-Pad5)") (class "Default")
      (node (ref "J4") (pin "5") (pinfunction "5_5") (pintype "passive"))
    )
    (net (code "101") (name "unconnected-(J4-Pad6)") (class "Default")
      (node (ref "J4") (pin "6") (pinfunction "6_6") (pintype "passive"))
    )
    (net (code "102") (name "unconnected-(J4-Pad7)") (class "Default")
      (node (ref "J4") (pin "7") (pinfunction "7_7") (pintype "passive"))
    )
    (net (code "103") (name "unconnected-(J4-Pad8)") (class "Default")
      (node (ref "J4") (pin "8") (pinfunction "8_8") (pintype "passive"))
    )
    (net (code "104") (name "unconnected-(J4-Pad9)") (class "Default")
      (node (ref "J4") (pin "9") (pinfunction "9_9") (pintype "passive"))
    )
    (net (code "105") (name "unconnected-(JP2-CD1-PadCD2)") (class "Default")
      (node (ref "JP2") (pin "CD2") (pinfunction "CD1_CD2") (pintype "bidirectional"))
    )
    (net (code "106") (name "unconnected-(JP2-CD2-PadGND2)") (class "Default")
      (node (ref "JP2") (pin "GND2") (pinfunction "CD2_GND2") (pintype "bidirectional"))
    )
    (net (code "107") (name "unconnected-(JP2-NC-Pad1)") (class "Default")
      (node (ref "JP2") (pin "1") (pinfunction "NC_1") (pintype "bidirectional"))
    )
    (net (code "108") (name "unconnected-(JP2-RSV-Pad8)") (class "Default")
      (node (ref "JP2") (pin "8") (pinfunction "RSV_8") (pintype "bidirectional"))
    )
    (net (code "109") (name "unconnected-(JP2-SHIELD-PadCD1)") (class "Default")
      (node (ref "JP2") (pin "CD1") (pinfunction "SHIELD_CD1") (pintype "bidirectional"))
    )
    (net (code "110") (name "unconnected-(JP2-SHIELD-PadGND1)") (class "Default")
      (node (ref "JP2") (pin "GND1") (pinfunction "SHIELD_GND1") (pintype "bidirectional"))
    )
    (net (code "111") (name "unconnected-(OSC1-TS-Pad1)") (class "Default")
      (node (ref "OSC1") (pin "1") (pinfunction "TS_1") (pintype "passive"))
    )
  )
)
